# PMW3360-breakout_02_v16.net
KiCad netlist of a schematic drawn in EAGLE
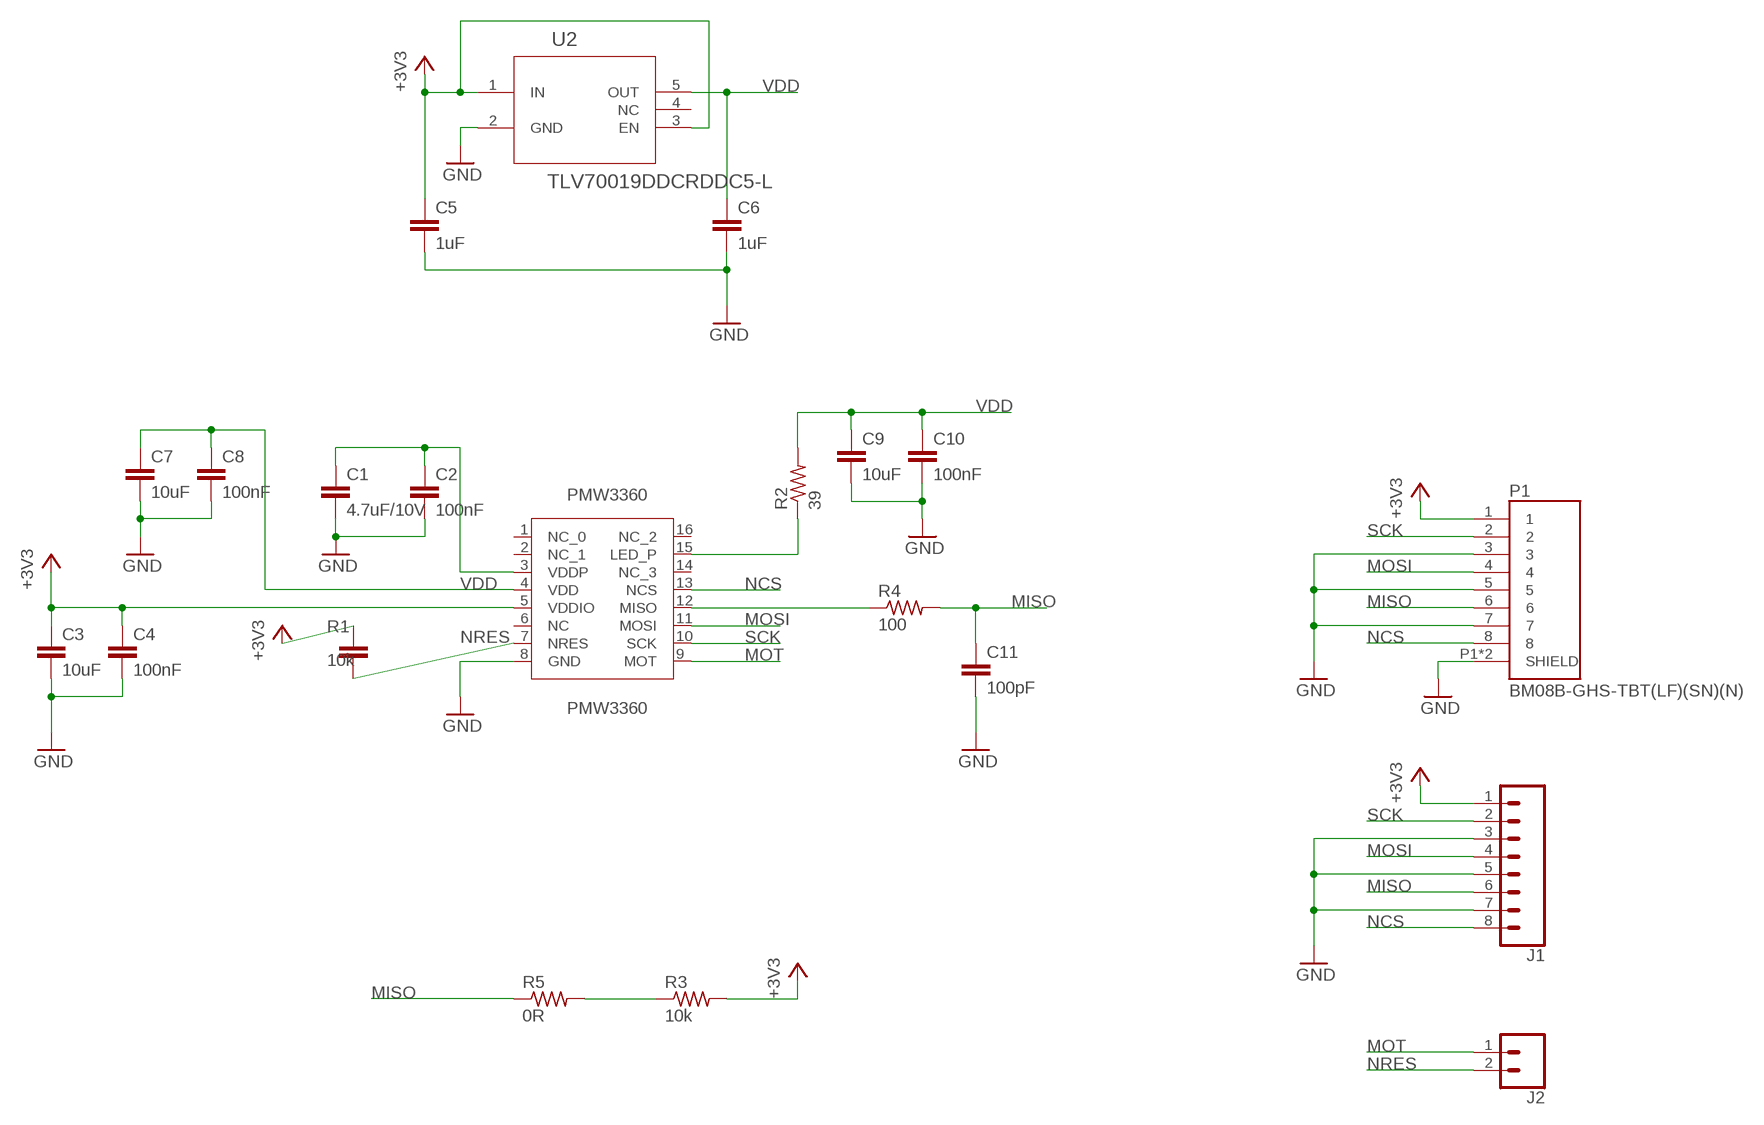
[diagram p0: schematic, sheet 1]

(export (version "E")
  (design (tool "Eeschema 10.0.6"))
  (components
    (comp (ref "C1")
      (value "4.7uF/10V")
      (footprint "eagle-import:CAPC1608X85")
      (libsource (lib "eagle-import") (part "CCHIP-0603(1608-METRIC)_"))
    )
    (comp (ref "C2")
      (value "100nF")
      (footprint "eagle-import:CAPC1005X60")
      (libsource (lib "eagle-import") (part "CCHIP-0402(1005-METRIC)_"))
    )
    (comp (ref "C3")
      (value "10uF")
      (footprint "eagle-import:CAPC1005X60")
      (libsource (lib "eagle-import") (part "CCHIP-0402(1005-METRIC)_"))
    )
    (comp (ref "C4")
      (value "100nF")
      (footprint "eagle-import:CAPC1005X60")
      (libsource (lib "eagle-import") (part "CCHIP-0402(1005-METRIC)_"))
    )
    (comp (ref "C5")
      (value "1uF")
      (footprint "eagle-import:CAPC1005X60")
      (libsource (lib "eagle-import") (part "CCHIP-0402(1005-METRIC)_"))
    )
    (comp (ref "C6")
      (value "1uF")
      (footprint "eagle-import:CAPC1005X60")
      (libsource (lib "eagle-import") (part "CCHIP-0402(1005-METRIC)_"))
    )
    (comp (ref "C7")
      (value "10uF")
      (footprint "eagle-import:CAPC1005X60")
      (libsource (lib "eagle-import") (part "CCHIP-0402(1005-METRIC)_"))
    )
    (comp (ref "C8")
      (value "100nF")
      (footprint "eagle-import:CAPC1005X60")
      (libsource (lib "eagle-import") (part "CCHIP-0402(1005-METRIC)_"))
    )
    (comp (ref "C9")
      (value "10uF")
      (footprint "eagle-import:CAPC1005X60")
      (libsource (lib "eagle-import") (part "CCHIP-0402(1005-METRIC)_"))
    )
    (comp (ref "C10")
      (value "100nF")
      (footprint "eagle-import:CAPC1005X60")
      (libsource (lib "eagle-import") (part "CCHIP-0402(1005-METRIC)_"))
    )
    (comp (ref "C11")
      (value "100pF")
      (footprint "eagle-import:CAPC1005X60")
      (libsource (lib "eagle-import") (part "CCHIP-0402(1005-METRIC)_"))
    )
    (comp (ref "J1")
      (value "CONN_08\"")
      (footprint "eagle-import:1X08")
      (libsource (lib "eagle-import") (part "CONN_08{dblquote}"))
    )
    (comp (ref "J2")
      (value "CONN_02")
      (footprint "eagle-import:1X02")
      (libsource (lib "eagle-import") (part "CONN_02"))
    )
    (comp (ref "P1")
      (value "BM08B-GHS-TBT(LF)(SN)(N)")
      (footprint "eagle-import:JST_BM08B-GHS-TBT(LF)(SN)(N)")
      (fields (field (name "MF") "JST Sales"))
      (libsource (lib "eagle-import") (part "BM08B-GHS-TBT(LF)(SN)(N)"))
    )
    (comp (ref "PMW3360")
      (value "PMW3360")
      (footprint "eagle-import:PMW3360")
      (libsource (lib "eagle-import") (part "PMW3360"))
    )
    (comp (ref "R1")
      (value "10k")
      (footprint "eagle-import:CAPC1005X60")
      (libsource (lib "eagle-import") (part "CCHIP-0402(1005-METRIC)_"))
    )
    (comp (ref "R2")
      (value "39")
      (footprint "eagle-import:R0402")
      (libsource (lib "eagle-import") (part "R-US_R0402"))
    )
    (comp (ref "R3")
      (value "10k")
      (footprint "eagle-import:R0402")
      (libsource (lib "eagle-import") (part "R-US_R0402"))
    )
    (comp (ref "R4")
      (value "100")
      (footprint "eagle-import:R0402")
      (libsource (lib "eagle-import") (part "R-US_R0402"))
    )
    (comp (ref "R5")
      (value "0R")
      (footprint "eagle-import:R0402")
      (libsource (lib "eagle-import") (part "R-US_R0402"))
    )
    (comp (ref "U2")
      (value "TLV70019DDCRDDC5-L")
      (footprint "eagle-import:DDC5-L")
      (fields
        (field (name "MANUFACTURER_PART_NUMBER") "TLV70019DDCR")
        (field (name "COPYRIGHT") "Copyright (C) 2024 Ultra Librarian. All rights reserved.")
      )
      (libsource (lib "eagle-import") (part "TLV70019DDCRDDC5-L"))
    )
  )
  (nets
    (net (code "1") (name "+3V3") (class "Default")
      (node (ref "C3") (pin "1") (pinfunction "1_1") (pintype "passive"))
      (node (ref "C4") (pin "1") (pinfunction "1_1") (pintype "passive"))
      (node (ref "C5") (pin "1") (pinfunction "1_1") (pintype "passive"))
      (node (ref "J1") (pin "1") (pinfunction "1_1") (pintype "passive"))
      (node (ref "P1") (pin "1") (pinfunction "1_1") (pintype "passive"))
      (node (ref "PMW3360") (pin "5") (pinfunction "VDDIO_5") (pintype "power_in"))
      (node (ref "R1") (pin "1") (pinfunction "1_1") (pintype "passive"))
      (node (ref "R3") (pin "2") (pinfunction "2_2") (pintype "passive"))
      (node (ref "U2") (pin "1") (pinfunction "IN_1") (pintype "input"))
      (node (ref "U2") (pin "3") (pinfunction "EN_3") (pintype "passive"))
    )
    (net (code "2") (name "/MISO") (class "Default")
      (node (ref "C11") (pin "1") (pinfunction "1_1") (pintype "passive"))
      (node (ref "J1") (pin "6") (pinfunction "6_6") (pintype "passive"))
      (node (ref "P1") (pin "6") (pinfunction "6_6") (pintype "passive"))
      (node (ref "R4") (pin "2") (pinfunction "2_2") (pintype "passive"))
      (node (ref "R5") (pin "1") (pinfunction "1_1") (pintype "passive"))
    )
    (net (code "3") (name "/MOSI") (class "Default")
      (node (ref "J1") (pin "4") (pinfunction "4_4") (pintype "passive"))
      (node (ref "P1") (pin "4") (pinfunction "4_4") (pintype "passive"))
      (node (ref "PMW3360") (pin "11") (pinfunction "MOSI_11") (pintype "input"))
    )
    (net (code "4") (name "/MOT") (class "Default")
      (node (ref "J2") (pin "1") (pinfunction "1_1") (pintype "passive"))
      (node (ref "PMW3360") (pin "9") (pinfunction "MOT_9") (pintype "output"))
    )
    (net (code "5") (name "/NCS") (class "Default")
      (node (ref "J1") (pin "8") (pinfunction "8_8") (pintype "passive"))
      (node (ref "P1") (pin "8") (pinfunction "8_8") (pintype "passive"))
      (node (ref "PMW3360") (pin "13") (pinfunction "NCS_13") (pintype "input"))
    )
    (net (code "6") (name "/NRES") (class "Default")
      (node (ref "J2") (pin "2") (pinfunction "2_2") (pintype "passive"))
      (node (ref "PMW3360") (pin "7") (pinfunction "NRES_7") (pintype "input"))
      (node (ref "R1") (pin "2") (pinfunction "2_2") (pintype "passive"))
    )
    (net (code "7") (name "/SCK") (class "Default")
      (node (ref "J1") (pin "2") (pinfunction "2_2") (pintype "passive"))
      (node (ref "P1") (pin "2") (pinfunction "2_2") (pintype "passive"))
      (node (ref "PMW3360") (pin "10") (pinfunction "SCK_10") (pintype "input"))
    )
    (net (code "8") (name "/VDD") (class "Default")
      (node (ref "C10") (pin "1") (pinfunction "1_1") (pintype "passive"))
      (node (ref "C6") (pin "1") (pinfunction "1_1") (pintype "passive"))
      (node (ref "C7") (pin "1") (pinfunction "1_1") (pintype "passive"))
      (node (ref "C8") (pin "1") (pinfunction "1_1") (pintype "passive"))
      (node (ref "C9") (pin "1") (pinfunction "1_1") (pintype "passive"))
      (node (ref "PMW3360") (pin "4") (pinfunction "VDD_4") (pintype "power_in"))
      (node (ref "R2") (pin "2") (pinfunction "2_2") (pintype "passive"))
      (node (ref "U2") (pin "5") (pinfunction "OUT_5") (pintype "output"))
    )
    (net (code "9") (name "GND") (class "Default")
      (node (ref "C1") (pin "2") (pinfunction "2_2") (pintype "passive"))
      (node (ref "C10") (pin "2") (pinfunction "2_2") (pintype "passive"))
      (node (ref "C11") (pin "2") (pinfunction "2_2") (pintype "passive"))
      (node (ref "C2") (pin "2") (pinfunction "2_2") (pintype "passive"))
      (node (ref "C3") (pin "2") (pinfunction "2_2") (pintype "passive"))
      (node (ref "C4") (pin "2") (pinfunction "2_2") (pintype "passive"))
      (node (ref "C5") (pin "2") (pinfunction "2_2") (pintype "passive"))
      (node (ref "C6") (pin "2") (pinfunction "2_2") (pintype "passive"))
      (node (ref "C7") (pin "2") (pinfunction "2_2") (pintype "passive"))
      (node (ref "C8") (pin "2") (pinfunction "2_2") (pintype "passive"))
      (node (ref "C9") (pin "2") (pinfunction "2_2") (pintype "passive"))
      (node (ref "J1") (pin "3") (pinfunction "3_3") (pintype "passive"))
      (node (ref "J1") (pin "5") (pinfunction "5_5") (pintype "passive"))
      (node (ref "J1") (pin "7") (pinfunction "7_7") (pintype "passive"))
      (node (ref "P1") (pin "3") (pinfunction "3_3") (pintype "passive"))
      (node (ref "P1") (pin "5") (pinfunction "5_5") (pintype "passive"))
      (node (ref "P1") (pin "7") (pinfunction "7_7") (pintype "passive"))
      (node (ref "P1") (pin "P1") (pinfunction "SHIELD_P1") (pintype "passive"))
      (node (ref "P1") (pin "P2") (pinfunction "SHIELD_P2") (pintype "passive"))
      (node (ref "PMW3360") (pin "8") (pinfunction "GND_8") (pintype "power_in"))
      (node (ref "U2") (pin "2") (pinfunction "GND_2") (pintype "power_in"))
    )
    (net (code "10") (name "Net-(PMW3360-LED_P)") (class "Default")
      (node (ref "PMW3360") (pin "15") (pinfunction "LED_P_15") (pintype "input"))
      (node (ref "R2") (pin "1") (pinfunction "1_1") (pintype "passive"))
    )
    (net (code "11") (name "Net-(PMW3360-MISO)") (class "Default")
      (node (ref "PMW3360") (pin "12") (pinfunction "MISO_12") (pintype "output"))
      (node (ref "R4") (pin "1") (pinfunction "1_1") (pintype "passive"))
    )
    (net (code "12") (name "Net-(PMW3360-VDDP)") (class "Default")
      (node (ref "C1") (pin "1") (pinfunction "1_1") (pintype "passive"))
      (node (ref "C2") (pin "1") (pinfunction "1_1") (pintype "passive"))
      (node (ref "PMW3360") (pin "3") (pinfunction "VDDP_3") (pintype "power_in"))
    )
    (net (code "13") (name "Net-(R3-Pad1)") (class "Default")
      (node (ref "R3") (pin "1") (pinfunction "1_1") (pintype "passive"))
      (node (ref "R5") (pin "2") (pinfunction "2_2") (pintype "passive"))
    )
    (net (code "14") (name "unconnected-(PMW3360-NC-Pad6)") (class "Default")
      (node (ref "PMW3360") (pin "6") (pinfunction "NC_6") (pintype "no_connect"))
    )
    (net (code "15") (name "unconnected-(PMW3360-NC_0-Pad1)") (class "Default")
      (node (ref "PMW3360") (pin "1") (pinfunction "NC_0_1") (pintype "no_connect"))
    )
    (net (code "16") (name "unconnected-(PMW3360-NC_1-Pad2)") (class "Default")
      (node (ref "PMW3360") (pin "2") (pinfunction "NC_1_2") (pintype "no_connect"))
    )
    (net (code "17") (name "unconnected-(PMW3360-NC_2-Pad16)") (class "Default")
      (node (ref "PMW3360") (pin "16") (pinfunction "NC_2_16") (pintype "no_connect"))
    )
    (net (code "18") (name "unconnected-(PMW3360-NC_3-Pad14)") (class "Default")
      (node (ref "PMW3360") (pin "14") (pinfunction "NC_3_14") (pintype "no_connect"))
    )
    (net (code "19") (name "unconnected-(U2-NC-Pad4)") (class "Default")
      (node (ref "U2") (pin "4") (pinfunction "NC_4") (pintype "passive"))
    )
  )
)
